# Power_Management_Battery_Monitor.net
KiCad netlist of a schematic drawn in Altium Designer
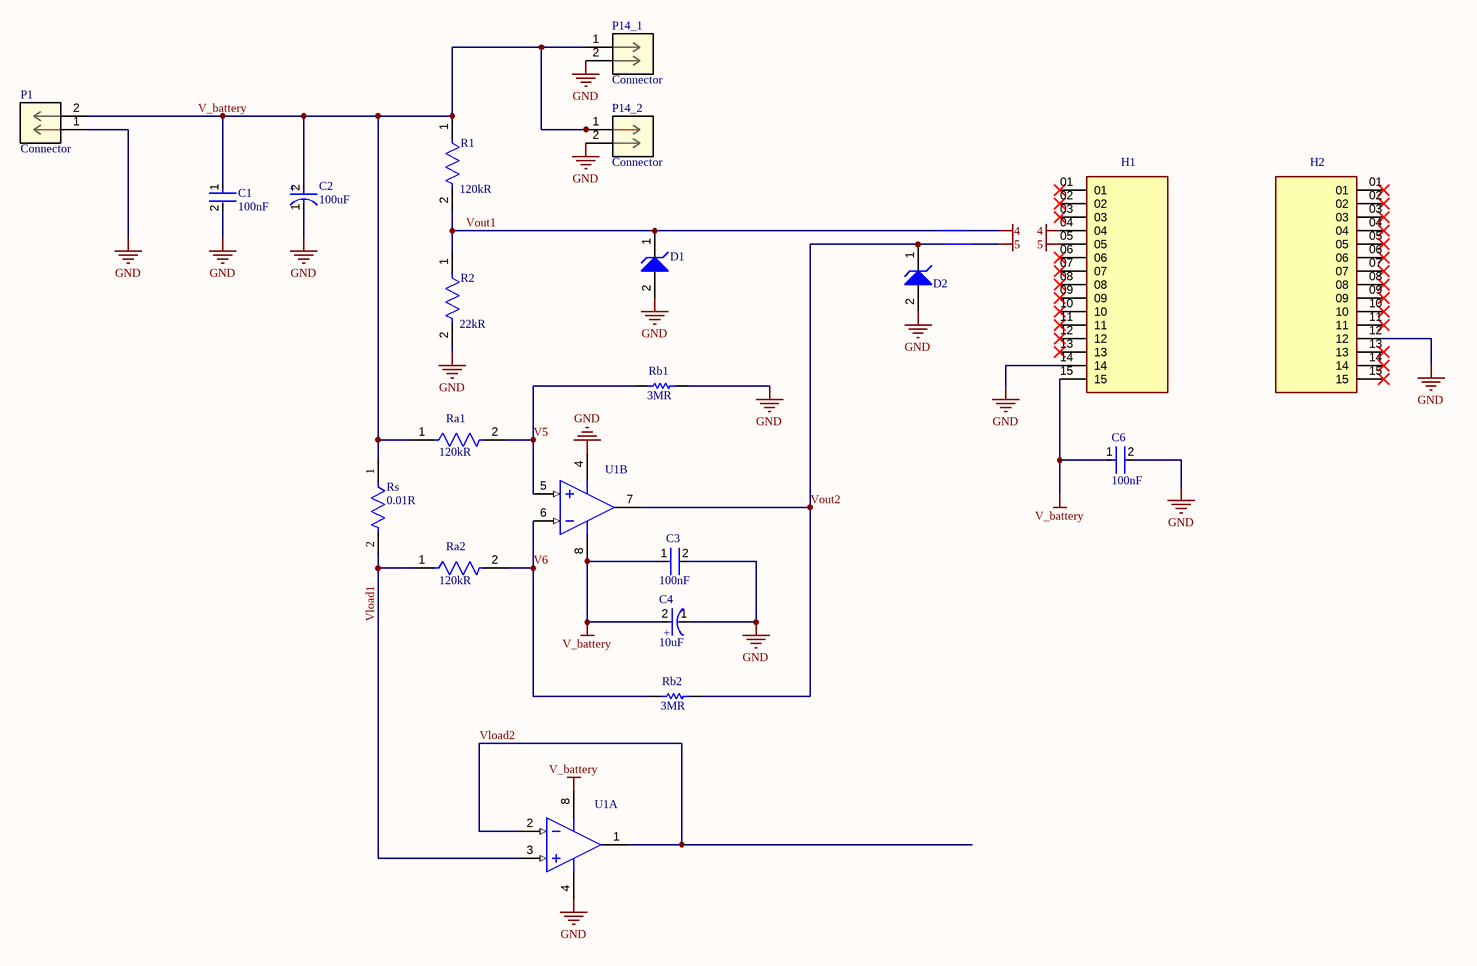
[diagram p0: Power Management & Battery Monitor.SchDoc]

(export (version "E")
  (design (tool "Eeschema 10.0.6"))
  (components
    (comp (ref "C1")
      (value "100nF")
      (footprint "FP-CC0805-0_85-IPC_A")
      (fields (field (name "Comment") "CC0805KRX7R8BB104"))
      (libsource (lib "Avery Cheng") (part "11868f565c42a9108669ba33697ecf6"))
    )
    (comp (ref "C2")
      (value "100uF")
      (footprint "FP-RAD-TH-D_6_3_0_5-L_11-MFG")
      (fields (field (name "Comment") "EEU-FR1E101B"))
      (libsource (lib "Avery Cheng") (part "a00bbbee19879c290e62620ae7e47b1"))
    )
    (comp (ref "C3")
      (value "100nF")
      (footprint "FP-CC0805-0_85-IPC_A")
      (fields (field (name "Comment") "CC0805KRX7R8BB104"))
      (libsource (lib "Avery Cheng") (part "11868f565c42a9108669ba33697ecf6"))
    )
    (comp (ref "C4")
      (value "10uF")
      (footprint "FP-FKB-MFG")
      (fields (field (name "Comment") "EEE-FK1E100R"))
      (libsource (lib "Avery Cheng") (part "203bc49f2ac43e59fd269a8c329ed05"))
    )
    (comp (ref "C6")
      (value "100nF")
      (footprint "FP-CC0805-0_85-IPC_A")
      (fields (field (name "Comment") "CC0805KRX7R8BB104"))
      (libsource (lib "Avery Cheng") (part "11868f565c42a9108669ba33697ecf6"))
    )
    (comp (ref "D1")
      (value "1SMA5918BT3G")
      (footprint "ONSC-SMA-2-403D-02_F_V")
      (description "Zener Diode, 5.1V V(Z), 5%, 0.5W, Silicon, Unidirectional")
      (libsource (lib "Avery Cheng") (part "ONSC-K1A2-2"))
    )
    (comp (ref "D2")
      (value "1SMA5918BT3G")
      (footprint "ONSC-SMA-2-403D-02_F_V")
      (description "Zener Diode, 5.1V V(Z), 5%, 0.5W, Silicon, Unidirectional")
      (libsource (lib "Avery Cheng") (part "ONSC-K1A2-2"))
    )
    (comp (ref "H1")
      (value "PPTC151LFBN-RC")
      (footprint "SAMTEC_DW-15-12-G-S-807")
      (fields (field (name "MANUFACTURER") "Sullins"))
      (libsource (lib "Schlib1") (part "PPTC151LFBN-RC"))
    )
    (comp (ref "H2")
      (value "PPTC151LFBN-RC")
      (footprint "SAMTEC_DW-15-12-G-S-807")
      (fields (field (name "MANUFACTURER") "Sullins"))
      (libsource (lib "") (part "PPTC151LFBN-RC_1"))
    )
    (comp (ref "NT2")
      (value "NetTie_SMD")
      (footprint "NetTie_SMD")
      (description "Net Tie SMD")
      (libsource (lib "Schlib1") (part "NetTie_SMD"))
    )
    (comp (ref "NT3")
      (value "NetTie_SMD")
      (footprint "NetTie_SMD")
      (description "Net Tie SMD")
      (libsource (lib "Schlib1") (part "NetTie_SMD"))
    )
    (comp (ref "P1")
      (value "Connector")
      (footprint "CONN_B2B-XH-A_JST")
      (description "Header B2B-XH-A, 2.50mm, 2-contacts, top entry, THT /1000/box")
      (fields (field (name "MANUFACTURER") "JST") (field (name "MANUFACTURER PART NUMBER") "B2B-XH-A"))
      (libsource (lib "") (part "B2B-XH-A_1"))
    )
    (comp (ref "P14_1")
      (value "Connector")
      (footprint "CONN_B2B-XH-A_JST")
      (description "Header B2B-XH-A, 2.50mm, 2-contacts, top entry, THT /1000/box")
      (fields (field (name "MANUFACTURER") "JST") (field (name "MANUFACTURER PART NUMBER") "B2B-XH-A"))
      (libsource (lib "Schlib1") (part "B2B-XH-A"))
    )
    (comp (ref "P14_2")
      (value "Connector")
      (footprint "CONN_B2B-XH-A_JST")
      (description "Header B2B-XH-A, 2.50mm, 2-contacts, top entry, THT /1000/box")
      (fields (field (name "MANUFACTURER") "JST") (field (name "MANUFACTURER PART NUMBER") "B2B-XH-A"))
      (libsource (lib "Schlib1") (part "B2B-XH-A"))
    )
    (comp (ref "R1")
      (value "120kR")
      (footprint "FP-RG2012-IPC_A")
      (description "Fixed Resistor, Thin Film, 0.125W, 120000ohm, 150V, 0.1% +/-Tol, 25ppm/Cel, Surface Mount, 0805")
      (fields (field (name "TOLERANCE") "0.1%") (field (name "POWER") "250mW"))
      (libsource (lib "Avery Cheng") (part "1029c3af85768c4190bb7ad29bc67b5"))
    )
    (comp (ref "R2")
      (value "22kR")
      (footprint "FP-RC0805-0_6-MFG")
      (fields
        (field (name "POWER") "125mW")
        (field (name "TOLERANCE") "1%")
        (field (name "Comment") "RC0805FR-0722KL")
      )
      (libsource (lib "Avery Cheng") (part "1029c3af85768c4190bb7ad29bc67b5"))
    )
    (comp (ref "Ra1")
      (value "120kR")
      (footprint "FP-RG2012-IPC_A")
      (description "Fixed Resistor, Thin Film, 0.125W, 120000ohm, 150V, 0.1% +/-Tol, 25ppm/Cel, Surface Mount, 0805")
      (fields (field (name "TOLERANCE") "0.1%") (field (name "POWER") "250mW"))
      (libsource (lib "Avery Cheng") (part "1029c3af85768c4190bb7ad29bc67b5"))
    )
    (comp (ref "Ra2")
      (value "120kR")
      (footprint "FP-RG2012-IPC_A")
      (description "Fixed Resistor, Thin Film, 0.125W, 120000ohm, 150V, 0.1% +/-Tol, 25ppm/Cel, Surface Mount, 0805")
      (fields (field (name "TOLERANCE") "0.1%") (field (name "POWER") "250mW"))
      (libsource (lib "Avery Cheng") (part "1029c3af85768c4190bb7ad29bc67b5"))
    )
    (comp (ref "Rb1")
      (value "3MR")
      (footprint "RESC3216X60X45NL10T20")
      (fields
        (field (name "POWER") "250mW")
        (field (name "TOLERANCE") "1%")
        (field (name "Comment") "CRCW12063M00FKEA")
      )
      (libsource (lib "Avery Cheng") (part "RES"))
    )
    (comp (ref "Rb2")
      (value "3MR")
      (footprint "RESC3216X60X45NL10T20")
      (fields
        (field (name "POWER") "250mW")
        (field (name "TOLERANCE") "1%")
        (field (name "Comment") "CRCW12063M00FKEA")
      )
      (libsource (lib "Avery Cheng") (part "RES"))
    )
    (comp (ref "Rs")
      (value "0.01R")
      (footprint "FP-FCSL110-0R002-0R100-IPC_C")
      (description "Fixed Resistor, Metal Foil, 5W, 0.01ohm, 1% +/-Tol, 50ppm/Cel, Surface Mount, 4320")
      (fields (field (name "TOLERANCE") "1%") (field (name "POWER") "5W"))
      (libsource (lib "Avery Cheng") (part "1029c3af85768c4190bb7ad29bc67b5"))
    )
    (comp (ref "U1")
      (value "OPA2192IDR")
      (footprint "D0008A_L")
      (description "Operational Amplifier, 2 Func, 25uV Offset-Max, BIPolar, PDSO8")
      (libsource (lib "Avery Cheng") (part "TI-OPA2192-8"))
    )
  )
  (nets
    (net (code "1") (name "/V5") (class "Default")
      (node (ref "Ra1") (pin "2") (pinfunction "2_2") (pintype "passive"))
      (node (ref "Rb1") (pin "1") (pinfunction "1_1") (pintype "passive"))
      (node (ref "U1") (pin "5") (pinfunction "IN_B+_5") (pintype "input"))
    )
    (net (code "2") (name "/V6") (class "Default")
      (node (ref "Ra2") (pin "2") (pinfunction "2_2") (pintype "passive"))
      (node (ref "Rb2") (pin "1") (pinfunction "1_1") (pintype "passive"))
      (node (ref "U1") (pin "6") (pinfunction "IN_B-_6") (pintype "input"))
    )
    (net (code "3") (name "/Vload1") (class "Default")
      (node (ref "Ra2") (pin "1") (pinfunction "1_1") (pintype "passive"))
      (node (ref "Rs") (pin "2") (pinfunction "2_2") (pintype "passive"))
      (node (ref "U1") (pin "3") (pinfunction "IN_A+_3") (pintype "input"))
    )
    (net (code "4") (name "/Vload2") (class "Default")
      (node (ref "U1") (pin "1") (pinfunction "OUT_A_1") (pintype "passive"))
      (node (ref "U1") (pin "2") (pinfunction "IN_A-_2") (pintype "input"))
    )
    (net (code "5") (name "/Vout1") (class "Default")
      (node (ref "D1") (pin "1") (pinfunction "K_1") (pintype "passive"))
      (node (ref "NT2") (pin "1") (pinfunction "1_1") (pintype "passive"))
      (node (ref "R1") (pin "2") (pinfunction "2_2") (pintype "passive"))
      (node (ref "R2") (pin "1") (pinfunction "1_1") (pintype "passive"))
    )
    (net (code "6") (name "/Vout2") (class "Default")
      (node (ref "D2") (pin "1") (pinfunction "K_1") (pintype "passive"))
      (node (ref "NT3") (pin "1") (pinfunction "1_1") (pintype "passive"))
      (node (ref "Rb2") (pin "2") (pinfunction "2_2") (pintype "passive"))
      (node (ref "U1") (pin "7") (pinfunction "OUT_B_7") (pintype "tri_state"))
    )
    (net (code "7") (name "4") (class "Default")
      (node (ref "H1") (pin "04") (pinfunction "04_04") (pintype "passive"))
      (node (ref "NT2") (pin "2") (pinfunction "2_2") (pintype "passive"))
    )
    (net (code "8") (name "5") (class "Default")
      (node (ref "H1") (pin "05") (pinfunction "05_05") (pintype "passive"))
      (node (ref "NT3") (pin "2") (pinfunction "2_2") (pintype "passive"))
    )
    (net (code "9") (name "GND") (class "Default")
      (node (ref "C1") (pin "2") (pinfunction "2_2") (pintype "passive"))
      (node (ref "C2") (pin "1") (pinfunction "C_1") (pintype "passive"))
      (node (ref "C3") (pin "2") (pinfunction "2_2") (pintype "passive"))
      (node (ref "C4") (pin "1") (pinfunction "C_1") (pintype "passive"))
      (node (ref "C6") (pin "2") (pinfunction "2_2") (pintype "passive"))
      (node (ref "D1") (pin "2") (pinfunction "A_2") (pintype "passive"))
      (node (ref "D2") (pin "2") (pinfunction "A_2") (pintype "passive"))
      (node (ref "H1") (pin "14") (pinfunction "14_14") (pintype "passive"))
      (node (ref "H2") (pin "12") (pinfunction "12_12") (pintype "passive"))
      (node (ref "P1") (pin "1") (pinfunction "1_1") (pintype "passive"))
      (node (ref "P14_1") (pin "2") (pinfunction "2_2") (pintype "passive"))
      (node (ref "P14_2") (pin "2") (pinfunction "2_2") (pintype "passive"))
      (node (ref "R2") (pin "2") (pinfunction "2_2") (pintype "passive"))
      (node (ref "Rb1") (pin "2") (pinfunction "2_2") (pintype "passive"))
      (node (ref "U1") (pin "4") (pinfunction "V-_4") (pintype "power_in"))
    )
    (net (code "10") (name "V_battery") (class "Default")
      (node (ref "C1") (pin "1") (pinfunction "1_1") (pintype "passive"))
      (node (ref "C2") (pin "2") (pinfunction "A_2") (pintype "passive"))
      (node (ref "C3") (pin "1") (pinfunction "1_1") (pintype "passive"))
      (node (ref "C4") (pin "2") (pinfunction "A_2") (pintype "passive"))
      (node (ref "C6") (pin "1") (pinfunction "1_1") (pintype "passive"))
      (node (ref "H1") (pin "15") (pinfunction "15_15") (pintype "passive"))
      (node (ref "P1") (pin "2") (pinfunction "2_2") (pintype "passive"))
      (node (ref "P14_1") (pin "1") (pinfunction "1_1") (pintype "passive"))
      (node (ref "P14_2") (pin "1") (pinfunction "1_1") (pintype "passive"))
      (node (ref "R1") (pin "1") (pinfunction "1_1") (pintype "passive"))
      (node (ref "Ra1") (pin "1") (pinfunction "1_1") (pintype "passive"))
      (node (ref "Rs") (pin "1") (pinfunction "1_1") (pintype "passive"))
      (node (ref "U1") (pin "8") (pinfunction "V+_8") (pintype "power_in"))
    )
    (net (code "11") (name "unconnected-(H1-Pad01)") (class "Default")
      (node (ref "H1") (pin "01") (pinfunction "01_01") (pintype "passive+no_connect"))
    )
    (net (code "12") (name "unconnected-(H1-Pad02)") (class "Default")
      (node (ref "H1") (pin "02") (pinfunction "02_02") (pintype "passive+no_connect"))
    )
    (net (code "13") (name "unconnected-(H1-Pad03)") (class "Default")
      (node (ref "H1") (pin "03") (pinfunction "03_03") (pintype "passive+no_connect"))
    )
    (net (code "14") (name "unconnected-(H1-Pad06)") (class "Default")
      (node (ref "H1") (pin "06") (pinfunction "06_06") (pintype "passive+no_connect"))
    )
    (net (code "15") (name "unconnected-(H1-Pad07)") (class "Default")
      (node (ref "H1") (pin "07") (pinfunction "07_07") (pintype "passive+no_connect"))
    )
    (net (code "16") (name "unconnected-(H1-Pad08)") (class "Default")
      (node (ref "H1") (pin "08") (pinfunction "08_08") (pintype "passive+no_connect"))
    )
    (net (code "17") (name "unconnected-(H1-Pad09)") (class "Default")
      (node (ref "H1") (pin "09") (pinfunction "09_09") (pintype "passive+no_connect"))
    )
    (net (code "18") (name "unconnected-(H1-Pad10)") (class "Default")
      (node (ref "H1") (pin "10") (pinfunction "10_10") (pintype "passive+no_connect"))
    )
    (net (code "19") (name "unconnected-(H1-Pad11)") (class "Default")
      (node (ref "H1") (pin "11") (pinfunction "11_11") (pintype "passive+no_connect"))
    )
    (net (code "20") (name "unconnected-(H1-Pad12)") (class "Default")
      (node (ref "H1") (pin "12") (pinfunction "12_12") (pintype "passive+no_connect"))
    )
    (net (code "21") (name "unconnected-(H1-Pad13)") (class "Default")
      (node (ref "H1") (pin "13") (pinfunction "13_13") (pintype "passive+no_connect"))
    )
    (net (code "22") (name "unconnected-(H2-Pad01)") (class "Default")
      (node (ref "H2") (pin "01") (pinfunction "01_01") (pintype "passive+no_connect"))
    )
    (net (code "23") (name "unconnected-(H2-Pad02)") (class "Default")
      (node (ref "H2") (pin "02") (pinfunction "02_02") (pintype "passive+no_connect"))
    )
    (net (code "24") (name "unconnected-(H2-Pad03)") (class "Default")
      (node (ref "H2") (pin "03") (pinfunction "03_03") (pintype "passive+no_connect"))
    )
    (net (code "25") (name "unconnected-(H2-Pad04)") (class "Default")
      (node (ref "H2") (pin "04") (pinfunction "04_04") (pintype "passive+no_connect"))
    )
    (net (code "26") (name "unconnected-(H2-Pad05)") (class "Default")
      (node (ref "H2") (pin "05") (pinfunction "05_05") (pintype "passive+no_connect"))
    )
    (net (code "27") (name "unconnected-(H2-Pad06)") (class "Default")
      (node (ref "H2") (pin "06") (pinfunction "06_06") (pintype "passive+no_connect"))
    )
    (net (code "28") (name "unconnected-(H2-Pad07)") (class "Default")
      (node (ref "H2") (pin "07") (pinfunction "07_07") (pintype "passive+no_connect"))
    )
    (net (code "29") (name "unconnected-(H2-Pad08)") (class "Default")
      (node (ref "H2") (pin "08") (pinfunction "08_08") (pintype "passive+no_connect"))
    )
    (net (code "30") (name "unconnected-(H2-Pad09)") (class "Default")
      (node (ref "H2") (pin "09") (pinfunction "09_09") (pintype "passive+no_connect"))
    )
    (net (code "31") (name "unconnected-(H2-Pad10)") (class "Default")
      (node (ref "H2") (pin "10") (pinfunction "10_10") (pintype "passive+no_connect"))
    )
    (net (code "32") (name "unconnected-(H2-Pad11)") (class "Default")
      (node (ref "H2") (pin "11") (pinfunction "11_11") (pintype "passive+no_connect"))
    )
    (net (code "33") (name "unconnected-(H2-Pad13)") (class "Default")
      (node (ref "H2") (pin "13") (pinfunction "13_13") (pintype "passive+no_connect"))
    )
    (net (code "34") (name "unconnected-(H2-Pad14)") (class "Default")
      (node (ref "H2") (pin "14") (pinfunction "14_14") (pintype "passive+no_connect"))
    )
    (net (code "35") (name "unconnected-(H2-Pad15)") (class "Default")
      (node (ref "H2") (pin "15") (pinfunction "15_15") (pintype "passive+no_connect"))
    )
  )
)
